# TPS22810_2_7_18V_3A_Load_Switch.net
KiCad netlist of a schematic drawn in Altium Designer
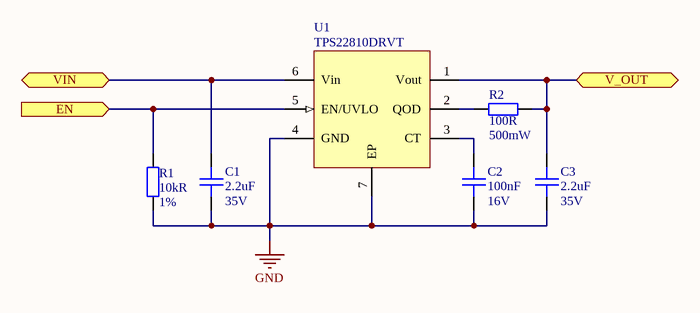
[diagram p0: TPS22810 2.7...18V 3A Load Switch.SchDoc]

(export (version "E")
  (design (tool "Eeschema 10.0.6"))
  (components
    (comp (ref "C1")
      (value "CAP CER 2.2UF 35V X5R 0603")
      (footprint "C0603")
      (description "2.2µF ±10% 35V Ceramic Capacitor X5R 0603 (1608 Metric)")
      (fields
        (field (name "MANUFACTURER") "Murata")
        (field (name "MANUFACTURER PART NUMBER") "GRM188R6YA225KA12D")
        (field (name "CAPACITANCE") "2.2uF")
        (field (name "VOLTAGE") "35V")
      )
      (libsource (lib "capacitors_smd") (part "CAP CER 2.2UF 35V X5R 0603"))
    )
    (comp (ref "C2")
      (value "CAP CER 0.1UF 16V X7R 0402")
      (footprint "C0402")
      (description "0.1µF ±10% 16V Ceramic Capacitor X7R 0402 (1005 Metric)")
      (fields
        (field (name "MANUFACTURER") "Yageo")
        (field (name "MANUFACTURER PART NUMBER") "CC0402KRX7R7BB104")
        (field (name "CAPACITANCE") "100nF")
        (field (name "VOLTAGE") "16V")
      )
      (libsource (lib "capacitors_smd") (part "CAP CER 0.1UF 16V X7R 0402"))
    )
    (comp (ref "C3")
      (value "CAP CER 2.2UF 35V X5R 0603")
      (footprint "C0603")
      (description "2.2µF ±10% 35V Ceramic Capacitor X5R 0603 (1608 Metric)")
      (fields
        (field (name "MANUFACTURER") "Murata")
        (field (name "MANUFACTURER PART NUMBER") "GRM188R6YA225KA12D")
        (field (name "CAPACITANCE") "2.2uF")
        (field (name "VOLTAGE") "35V")
      )
      (libsource (lib "capacitors_smd") (part "CAP CER 2.2UF 35V X5R 0603"))
    )
    (comp (ref "R1")
      (value "RES SMD 10K OHM 1% 1/16W 0402")
      (footprint "R0402")
      (description "10 kOhms ±1% 0.063W, 1/16W Chip Resistor 0402 (1005 Metric) Moisture Resistant Thick Film")
      (fields
        (field (name "MANUFACTURER") "Yageo")
        (field (name "MANUFACTURER PART NUMBER") "RC0402FR-0710KP")
        (field (name "RESISTANCE") "10kR")
        (field (name "TOLERANCE") "1%")
      )
      (libsource (lib "resistors_smd") (part "RES SMD 10K OHM 1% 1/16W 0402"))
    )
    (comp (ref "R2")
      (value "RES SMD 100 OHM 1% 1/2W 0805")
      (footprint "R0805")
      (fields
        (field (name "MANUFACTURER") "Panasonic")
        (field (name "MANUFACTURER PART NUMBER") "ERJ-P6WF1000V")
        (field (name "TOLERANCE") "1%")
        (field (name "RESISTANCE") "100R")
        (field (name "POWER RATING") "500mW")
      )
      (libsource (lib "resistors_smd") (part "RES SMD 100 OHM 1% 1/2W 0805"))
    )
    (comp (ref "U1")
      (value "TPS22810DRVT")
      (footprint "WSON-6 065")
      (description "TPS22810, 2.7-18-V, 79-mOhm On-Resistance Load Switch With Thermal Protection")
      (fields (field (name "MANUFACTURER") "Texas Instruments"))
      (libsource (lib "load_switches") (part "IC TPS22810DRVT PWR SWITCH N-CHAN 1{colon}1 6WSON"))
    )
  )
  (nets
    (net (code "1") (name "/EN") (class "Default")
      (node (ref "R1") (pin "1") (pinfunction "1_1") (pintype "passive"))
      (node (ref "U1") (pin "5") (pinfunction "EN/UVLO_5") (pintype "input"))
    )
    (net (code "2") (name "/VIN") (class "Default")
      (node (ref "C1") (pin "1") (pinfunction "1_1") (pintype "passive"))
      (node (ref "U1") (pin "6") (pinfunction "Vin_6") (pintype "power_in"))
    )
    (net (code "3") (name "/V_OUT") (class "Default")
      (node (ref "C3") (pin "1") (pinfunction "1_1") (pintype "passive"))
      (node (ref "R2") (pin "2") (pinfunction "2_2") (pintype "passive"))
      (node (ref "U1") (pin "1") (pinfunction "Vout_1") (pintype "power_in"))
    )
    (net (code "4") (name "GND") (class "Default")
      (node (ref "C1") (pin "2") (pinfunction "2_2") (pintype "passive"))
      (node (ref "C2") (pin "2") (pinfunction "2_2") (pintype "passive"))
      (node (ref "C3") (pin "2") (pinfunction "2_2") (pintype "passive"))
      (node (ref "R1") (pin "2") (pinfunction "2_2") (pintype "passive"))
      (node (ref "U1") (pin "4") (pinfunction "GND_4") (pintype "power_in"))
      (node (ref "U1") (pin "7") (pinfunction "EP_7") (pintype "passive"))
    )
    (net (code "5") (name "Net-(U1-CT)") (class "Default")
      (node (ref "C2") (pin "1") (pinfunction "1_1") (pintype "passive"))
      (node (ref "U1") (pin "3") (pinfunction "CT_3") (pintype "passive"))
    )
    (net (code "6") (name "Net-(U1-QOD)") (class "Default")
      (node (ref "R2") (pin "1") (pinfunction "1_1") (pintype "passive"))
      (node (ref "U1") (pin "2") (pinfunction "QOD_2") (pintype "passive"))
    )
  )
)
